# MCU.net
KiCad netlist of a schematic drawn in Altium Designer
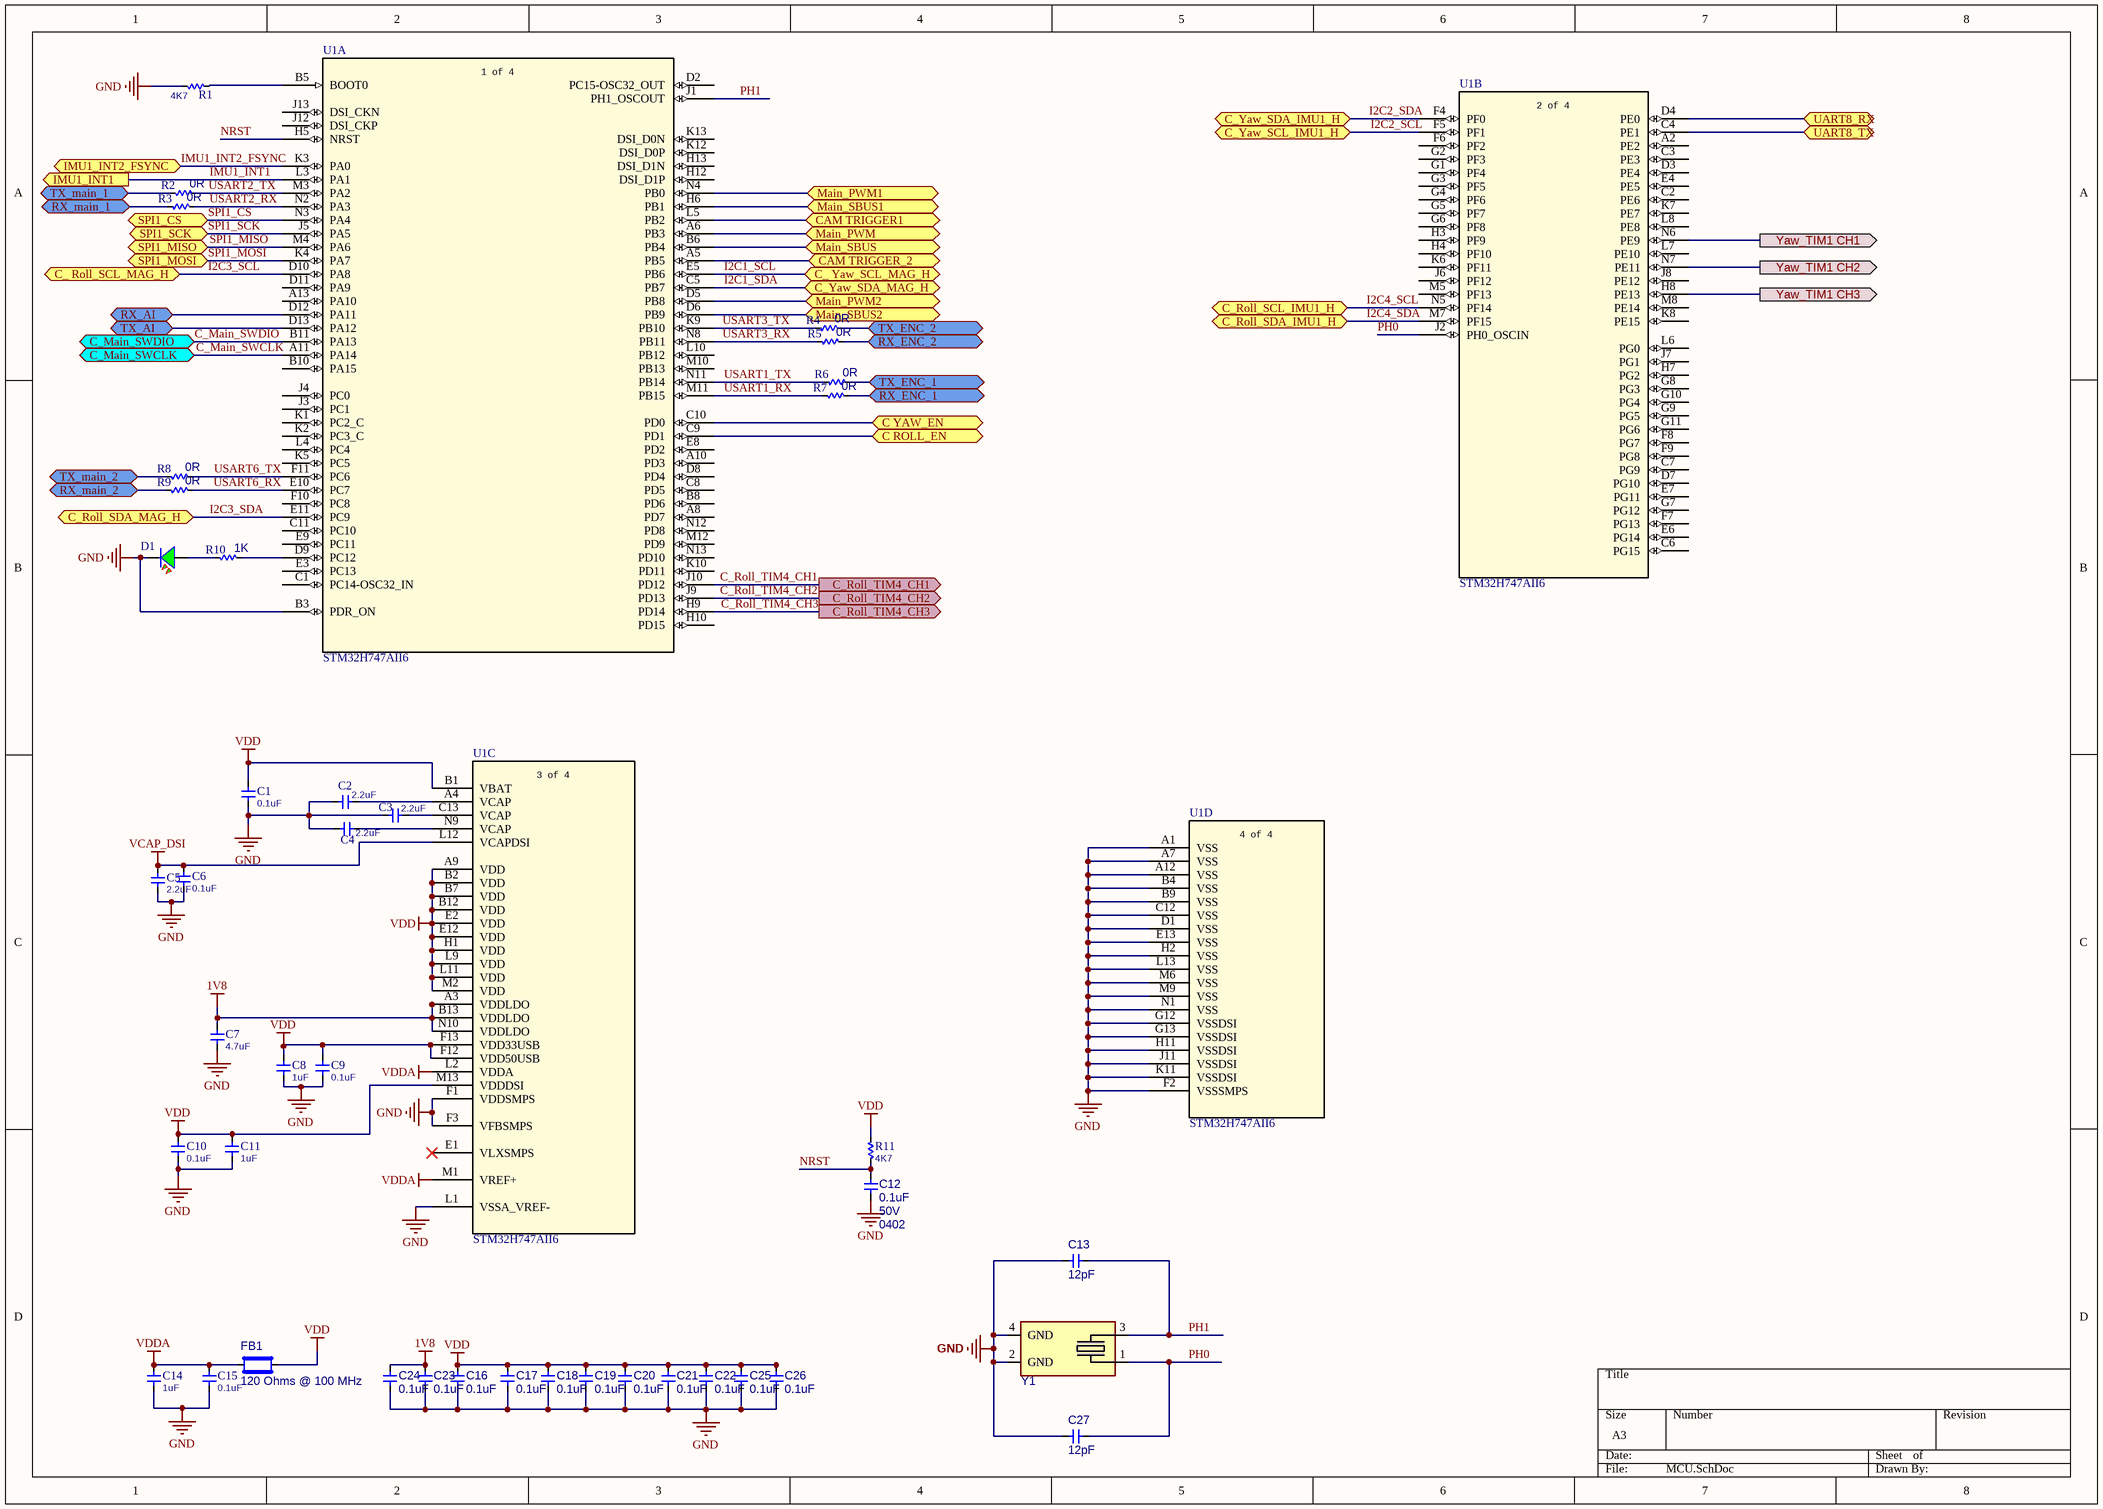
[diagram p0: MCU.SchDoc]

(export (version "E")
  (design (tool "Eeschema 10.0.6"))
  (components
    (comp (ref "C1")
      (value "0.1uF")
      (footprint "CAP0402")
      (description "Cap 0402")
      (fields (field (name "MP") "add later") (field (name "Comment") "CAP0402"))
      (libsource (lib "RTR") (part "CAP0402"))
    )
    (comp (ref "C2")
      (value "2.2uF")
      (footprint "CAP0402")
      (description "Cap 0402")
      (fields (field (name "MP") "add later") (field (name "Comment") "CAP0402"))
      (libsource (lib "RTR") (part "CAP0402"))
    )
    (comp (ref "C3")
      (value "2.2uF")
      (footprint "CAP0402")
      (description "Cap 0402")
      (fields (field (name "MP") "add later") (field (name "Comment") "CAP0402"))
      (libsource (lib "RTR") (part "CAP0402"))
    )
    (comp (ref "C4")
      (value "2.2uF")
      (footprint "CAP0402")
      (description "Cap 0402")
      (fields (field (name "MP") "add later") (field (name "Comment") "CAP0402"))
      (libsource (lib "RTR") (part "CAP0402"))
    )
    (comp (ref "C5")
      (value "2.2uF")
      (footprint "CAP0402")
      (description "Cap 0402")
      (fields (field (name "MP") "add later") (field (name "Comment") "CAP0402"))
      (libsource (lib "RTR") (part "CAP0402"))
    )
    (comp (ref "C6")
      (value "0.1uF")
      (footprint "CAP0402")
      (description "Cap 0402")
      (fields (field (name "MP") "add later") (field (name "Comment") "CAP0402"))
      (libsource (lib "RTR") (part "CAP0402"))
    )
    (comp (ref "C7")
      (value "4.7uF")
      (footprint "CAP0402")
      (description "Cap 0402")
      (fields (field (name "MP") "add later") (field (name "Comment") "CAP0402"))
      (libsource (lib "RTR") (part "CAP0402"))
    )
    (comp (ref "C8")
      (value "1uF")
      (footprint "CAP0402")
      (description "Cap 0402")
      (fields (field (name "MP") "add later") (field (name "Comment") "CAP0402"))
      (libsource (lib "RTR") (part "CAP0402"))
    )
    (comp (ref "C9")
      (value "0.1uF")
      (footprint "CAP0402")
      (description "Cap 0402")
      (fields (field (name "MP") "add later") (field (name "Comment") "CAP0402"))
      (libsource (lib "RTR") (part "CAP0402"))
    )
    (comp (ref "C10")
      (value "0.1uF")
      (footprint "CAP0402")
      (description "Cap 0402")
      (fields (field (name "MP") "add later") (field (name "Comment") "CAP0402"))
      (libsource (lib "RTR") (part "CAP0402"))
    )
    (comp (ref "C11")
      (value "1uF")
      (footprint "CAP0402")
      (description "Cap 0402")
      (fields (field (name "MP") "add later") (field (name "Comment") "CAP0402"))
      (libsource (lib "RTR") (part "CAP0402"))
    )
    (comp (ref "C12")
      (value "0.1uF")
      (footprint "CAP0402")
      (description "Cap 0.1uF 50V 0402")
      (fields
        (field (name "MP") "CC0402KRX5R9BB104")
        (field (name "VOLTAGE") "50V")
        (field (name "PACKAGE") "0402")
        (field (name "Comment") "CAP0402 0.1uF 50V")
      )
      (libsource (lib "RTR") (part "CAP0402 0.1uF 50V"))
    )
    (comp (ref "C13")
      (value "12pF")
      (footprint "CAP0402")
      (description "Cap 12pF 50V 0402")
      (fields (field (name "Comment") "CAP0402 12pF 50V"))
      (libsource (lib "RTR") (part "CAP0402 12pF 50V"))
    )
    (comp (ref "C14")
      (value "1uF")
      (footprint "CAP0402")
      (description "Cap 0402")
      (fields (field (name "MP") "add later") (field (name "Comment") "CAP0402"))
      (libsource (lib "RTR") (part "CAP0402"))
    )
    (comp (ref "C15")
      (value "0.1uF")
      (footprint "CAP0402")
      (description "Cap 0402")
      (fields (field (name "MP") "add later") (field (name "Comment") "CAP0402"))
      (libsource (lib "RTR") (part "CAP0402"))
    )
    (comp (ref "C16")
      (value "0.1uF")
      (footprint "CAP0402")
      (description "Cap 0.1uF 50V 0402")
      (fields (field (name "MP") "CC0402KRX5R9BB104") (field (name "VOLTAGE") "50V"))
      (libsource (lib "RTR") (part "CAP0402 0.1uF 50V"))
    )
    (comp (ref "C17")
      (value "0.1uF")
      (footprint "CAP0402")
      (description "Cap 0.1uF 50V 0402")
      (fields (field (name "MP") "CC0402KRX5R9BB104") (field (name "VOLTAGE") "50V"))
      (libsource (lib "RTR") (part "CAP0402 0.1uF 50V"))
    )
    (comp (ref "C18")
      (value "0.1uF")
      (footprint "CAP0402")
      (description "Cap 0.1uF 50V 0402")
      (fields (field (name "MP") "CC0402KRX5R9BB104") (field (name "VOLTAGE") "50V"))
      (libsource (lib "RTR") (part "CAP0402 0.1uF 50V"))
    )
    (comp (ref "C19")
      (value "0.1uF")
      (footprint "CAP0402")
      (description "Cap 0.1uF 50V 0402")
      (fields (field (name "MP") "CC0402KRX5R9BB104") (field (name "VOLTAGE") "50V"))
      (libsource (lib "RTR") (part "CAP0402 0.1uF 50V"))
    )
    (comp (ref "C20")
      (value "0.1uF")
      (footprint "CAP0402")
      (description "Cap 0.1uF 50V 0402")
      (fields (field (name "MP") "CC0402KRX5R9BB104") (field (name "VOLTAGE") "50V"))
      (libsource (lib "RTR") (part "CAP0402 0.1uF 50V"))
    )
    (comp (ref "C21")
      (value "0.1uF")
      (footprint "CAP0402")
      (description "Cap 0.1uF 50V 0402")
      (fields (field (name "MP") "CC0402KRX5R9BB104") (field (name "VOLTAGE") "50V"))
      (libsource (lib "RTR") (part "CAP0402 0.1uF 50V"))
    )
    (comp (ref "C22")
      (value "0.1uF")
      (footprint "CAP0402")
      (description "Cap 0.1uF 50V 0402")
      (fields (field (name "MP") "CC0402KRX5R9BB104") (field (name "VOLTAGE") "50V"))
      (libsource (lib "RTR") (part "CAP0402 0.1uF 50V"))
    )
    (comp (ref "C23")
      (value "0.1uF")
      (footprint "CAP0402")
      (description "Cap 0.1uF 50V 0402")
      (fields (field (name "MP") "CC0402KRX5R9BB104") (field (name "VOLTAGE") "50V"))
      (libsource (lib "RTR") (part "CAP0402 0.1uF 50V"))
    )
    (comp (ref "C24")
      (value "0.1uF")
      (footprint "CAP0402")
      (description "Cap 0.1uF 50V 0402")
      (fields (field (name "MP") "CC0402KRX5R9BB104") (field (name "VOLTAGE") "50V"))
      (libsource (lib "RTR") (part "CAP0402 0.1uF 50V"))
    )
    (comp (ref "C25")
      (value "0.1uF")
      (footprint "CAP0402")
      (description "Cap 0.1uF 50V 0402")
      (fields (field (name "MP") "CC0402KRX5R9BB104") (field (name "VOLTAGE") "50V"))
      (libsource (lib "RTR") (part "CAP0402 0.1uF 50V"))
    )
    (comp (ref "C26")
      (value "0.1uF")
      (footprint "CAP0402")
      (description "Cap 0.1uF 50V 0402")
      (fields (field (name "MP") "CC0402KRX5R9BB104") (field (name "VOLTAGE") "50V"))
      (libsource (lib "RTR") (part "CAP0402 0.1uF 50V"))
    )
    (comp (ref "C27")
      (value "12pF")
      (footprint "CAP0402")
      (description "Cap 12pF 50V 0402")
      (fields (field (name "Comment") "CAP0402 12pF 50V"))
      (libsource (lib "RTR") (part "CAP0402 12pF 50V"))
    )
    (comp (ref "D1")
      (value "SML-310MTT86")
      (footprint "LED0603 GREEN")
      (description "LED GREEN CLEAR 0603 SMD")
      (libsource (lib "HeraJetson_Modified") (part "CMP-01130-2"))
    )
    (comp (ref "FB1")
      (value "BLM15PX121SZ1D")
      (footprint "FERRIT0402")
      (description "120 Ohms @ 100 MHz 1 Power Line Ferrite Bead 0402 (1005 Metric) 2A 55mOhm")
      (fields (field (name "IMPEDANCE @ FREQUENCY") "120 Ohms @ 100 MHz"))
      (libsource (lib "RTR") (part "BLM15PX121SZ1D"))
    )
    (comp (ref "R1")
      (value "4K7")
      (footprint "RES0402")
      (description "RES 4K7 0402")
      (fields (field (name "MP") "RC0402JR-074K7L") (field (name "Comment") "RES0402 4K7"))
      (libsource (lib "RTR") (part "RES0402 4K7"))
    )
    (comp (ref "R2")
      (value "0R")
      (footprint "RES0402")
      (description "RES 0R 0402")
      (fields (field (name "MP") "RC0402JR-070RL") (field (name "Comment") "RES0402 0R"))
      (libsource (lib "RTR") (part "RES0402 0R"))
    )
    (comp (ref "R3")
      (value "0R")
      (footprint "RES0402")
      (description "RES 0R 0402")
      (fields (field (name "MP") "RC0402JR-070RL") (field (name "Comment") "RES0402 0R"))
      (libsource (lib "RTR") (part "RES0402 0R"))
    )
    (comp (ref "R4")
      (value "0R")
      (footprint "RES0402")
      (description "RES 0R 0402")
      (fields (field (name "MP") "RC0402JR-070RL") (field (name "Comment") "RES0402 0R"))
      (libsource (lib "RTR") (part "RES0402 0R"))
    )
    (comp (ref "R5")
      (value "0R")
      (footprint "RES0402")
      (description "RES 0R 0402")
      (fields (field (name "MP") "RC0402JR-070RL") (field (name "Comment") "RES0402 0R"))
      (libsource (lib "RTR") (part "RES0402 0R"))
    )
    (comp (ref "R6")
      (value "0R")
      (footprint "RES0402")
      (description "RES 0R 0402")
      (fields (field (name "MP") "RC0402JR-070RL") (field (name "Comment") "RES0402 0R"))
      (libsource (lib "RTR") (part "RES0402 0R"))
    )
    (comp (ref "R7")
      (value "0R")
      (footprint "RES0402")
      (description "RES 0R 0402")
      (fields (field (name "MP") "RC0402JR-070RL") (field (name "Comment") "RES0402 0R"))
      (libsource (lib "RTR") (part "RES0402 0R"))
    )
    (comp (ref "R8")
      (value "0R")
      (footprint "RES0402")
      (description "RES 0R 0402")
      (fields (field (name "MP") "RC0402JR-070RL") (field (name "Comment") "RES0402 0R"))
      (libsource (lib "RTR") (part "RES0402 0R"))
    )
    (comp (ref "R9")
      (value "0R")
      (footprint "RES0402")
      (description "RES 0R 0402")
      (fields (field (name "MP") "RC0402JR-070RL") (field (name "Comment") "RES0402 0R"))
      (libsource (lib "RTR") (part "RES0402 0R"))
    )
    (comp (ref "R10")
      (value "1K")
      (footprint "RES0402")
      (description "RES 0R 0402")
      (fields (field (name "MP") "RC0402JR-070RL") (field (name "Comment") "RES0402 0R"))
      (libsource (lib "RTR") (part "RES0402 0R"))
    )
    (comp (ref "R11")
      (value "4K7")
      (footprint "RES0402")
      (description "RES 4K7 0402")
      (fields (field (name "MP") "RC0402JR-074K7L") (field (name "Comment") "RES0402 4K7"))
      (libsource (lib "RTR") (part "RES0402 4K7"))
    )
    (comp (ref "U1")
      (value "STM32H747AII6")
      (footprint "UFBGA169")
      (fields (field (name "COPYRIGHT") "Copyright (C) 2026 Ultra Librarian. All rights reserved."))
      (libsource (lib "RTR") (part "STM32H747AII6"))
    )
    (comp (ref "Y1")
      (value "ECS-240-12-37B-CKY-TR")
      (footprint "XTAL_ECS-240-12-37B-CKY-TR")
      (description "Crystal 24 MHz ±10ppm 12pF 50 Ohms 4-SMD, No Lead")
      (libsource (lib "RTR") (part "ECS-240-12-37B-CKY-TR"))
    )
  )
  (nets
    (net (code "1") (name "/C ROLL_EN") (class "Default")
      (node (ref "U1") (pin "C9") (pinfunction "PD1_C9") (pintype "bidirectional"))
    )
    (net (code "2") (name "/C YAW_EN") (class "Default")
      (node (ref "U1") (pin "C10") (pinfunction "PD0_C10") (pintype "bidirectional"))
    )
    (net (code "3") (name "/CAM TRIGGER1") (class "Default")
      (node (ref "U1") (pin "L5") (pinfunction "PB2_L5") (pintype "bidirectional"))
    )
    (net (code "4") (name "/CAM TRIGGER_2") (class "Default")
      (node (ref "U1") (pin "A5") (pinfunction "PB5_A5") (pintype "bidirectional"))
    )
    (net (code "5") (name "/C_Main_SWCLK") (class "Default")
      (node (ref "U1") (pin "A11") (pinfunction "PA14_A11") (pintype "bidirectional"))
    )
    (net (code "6") (name "/C_Main_SWDIO") (class "Default")
      (node (ref "U1") (pin "B11") (pinfunction "PA13_B11") (pintype "bidirectional"))
    )
    (net (code "7") (name "/C_Roll_TIM4_CH1") (class "Default")
      (node (ref "U1") (pin "J10") (pinfunction "PD12_J10") (pintype "bidirectional"))
    )
    (net (code "8") (name "/C_Roll_TIM4_CH2") (class "Default")
      (node (ref "U1") (pin "J9") (pinfunction "PD13_J9") (pintype "bidirectional"))
    )
    (net (code "9") (name "/C_Roll_TIM4_CH3") (class "Default")
      (node (ref "U1") (pin "H9") (pinfunction "PD14_H9") (pintype "bidirectional"))
    )
    (net (code "10") (name "/I2C1_SCL") (class "Default")
      (node (ref "U1") (pin "E5") (pinfunction "PB6_E5") (pintype "bidirectional"))
    )
    (net (code "11") (name "/I2C1_SDA") (class "Default")
      (node (ref "U1") (pin "C5") (pinfunction "PB7_C5") (pintype "bidirectional"))
    )
    (net (code "12") (name "/I2C2_SCL") (class "Default")
      (node (ref "U1") (pin "F5") (pinfunction "PF1_F5") (pintype "bidirectional"))
    )
    (net (code "13") (name "/I2C2_SDA") (class "Default")
      (node (ref "U1") (pin "F4") (pinfunction "PF0_F4") (pintype "bidirectional"))
    )
    (net (code "14") (name "/I2C3_SCL") (class "Default")
      (node (ref "U1") (pin "D10") (pinfunction "PA8_D10") (pintype "bidirectional"))
    )
    (net (code "15") (name "/I2C3_SDA") (class "Default")
      (node (ref "U1") (pin "E11") (pinfunction "PC9_E11") (pintype "bidirectional"))
    )
    (net (code "16") (name "/I2C4_SCL") (class "Default")
      (node (ref "U1") (pin "N5") (pinfunction "PF14_N5") (pintype "bidirectional"))
    )
    (net (code "17") (name "/I2C4_SDA") (class "Default")
      (node (ref "U1") (pin "M7") (pinfunction "PF15_M7") (pintype "bidirectional"))
    )
    (net (code "18") (name "/IMU1_INT1") (class "Default")
      (node (ref "U1") (pin "L3") (pinfunction "PA1_L3") (pintype "bidirectional"))
    )
    (net (code "19") (name "/IMU1_INT2_FSYNC") (class "Default")
      (node (ref "U1") (pin "K3") (pinfunction "PA0_K3") (pintype "bidirectional"))
    )
    (net (code "20") (name "/Main_PWM") (class "Default")
      (node (ref "U1") (pin "A6") (pinfunction "PB3_A6") (pintype "bidirectional"))
    )
    (net (code "21") (name "/Main_PWM1") (class "Default")
      (node (ref "U1") (pin "N4") (pinfunction "PB0_N4") (pintype "bidirectional"))
    )
    (net (code "22") (name "/Main_PWM2") (class "Default")
      (node (ref "U1") (pin "D5") (pinfunction "PB8_D5") (pintype "bidirectional"))
    )
    (net (code "23") (name "/Main_SBUS") (class "Default")
      (node (ref "U1") (pin "B6") (pinfunction "PB4_B6") (pintype "bidirectional"))
    )
    (net (code "24") (name "/Main_SBUS1") (class "Default")
      (node (ref "U1") (pin "H6") (pinfunction "PB1_H6") (pintype "bidirectional"))
    )
    (net (code "25") (name "/Main_SBUS2") (class "Default")
      (node (ref "U1") (pin "D6") (pinfunction "PB9_D6") (pintype "bidirectional"))
    )
    (net (code "26") (name "/NRST") (class "Default")
      (node (ref "C12") (pin "2") (pinfunction "2_2") (pintype "passive"))
      (node (ref "R11") (pin "1") (pinfunction "1_1") (pintype "passive"))
      (node (ref "U1") (pin "H5") (pinfunction "NRST_H5") (pintype "bidirectional"))
    )
    (net (code "27") (name "/PH0") (class "Default")
      (node (ref "C27") (pin "1") (pinfunction "1_1") (pintype "passive"))
      (node (ref "U1") (pin "J2") (pinfunction "PH0_OSCIN_J2") (pintype "bidirectional"))
      (node (ref "Y1") (pin "1") (pinfunction "IO_1") (pintype "passive"))
    )
    (net (code "28") (name "/PH1") (class "Default")
      (node (ref "C13") (pin "1") (pinfunction "1_1") (pintype "passive"))
      (node (ref "U1") (pin "J1") (pinfunction "PH1_OSCOUT_J1") (pintype "bidirectional"))
      (node (ref "Y1") (pin "3") (pinfunction "IO_3") (pintype "passive"))
    )
    (net (code "29") (name "/RX_AI") (class "Default")
      (node (ref "U1") (pin "D12") (pinfunction "PA11_D12") (pintype "bidirectional"))
    )
    (net (code "30") (name "/RX_ENC_1") (class "Default")
      (node (ref "R7") (pin "2") (pinfunction "2_2") (pintype "passive"))
    )
    (net (code "31") (name "/RX_ENC_2") (class "Default")
      (node (ref "R5") (pin "2") (pinfunction "2_2") (pintype "passive"))
    )
    (net (code "32") (name "/RX_main_1") (class "Default")
      (node (ref "R3") (pin "1") (pinfunction "1_1") (pintype "passive"))
    )
    (net (code "33") (name "/RX_main_2") (class "Default")
      (node (ref "R9") (pin "1") (pinfunction "1_1") (pintype "passive"))
    )
    (net (code "34") (name "/SPI1_CS") (class "Default")
      (node (ref "U1") (pin "N3") (pinfunction "PA4_N3") (pintype "bidirectional"))
    )
    (net (code "35") (name "/SPI1_MISO") (class "Default")
      (node (ref "U1") (pin "M4") (pinfunction "PA6_M4") (pintype "bidirectional"))
    )
    (net (code "36") (name "/SPI1_MOSI") (class "Default")
      (node (ref "U1") (pin "K4") (pinfunction "PA7_K4") (pintype "bidirectional"))
    )
    (net (code "37") (name "/SPI1_SCK") (class "Default")
      (node (ref "U1") (pin "J5") (pinfunction "PA5_J5") (pintype "bidirectional"))
    )
    (net (code "38") (name "/TX_AI") (class "Default")
      (node (ref "U1") (pin "D13") (pinfunction "PA12_D13") (pintype "bidirectional"))
    )
    (net (code "39") (name "/TX_ENC_1") (class "Default")
      (node (ref "R6") (pin "2") (pinfunction "2_2") (pintype "passive"))
    )
    (net (code "40") (name "/TX_ENC_2") (class "Default")
      (node (ref "R4") (pin "2") (pinfunction "2_2") (pintype "passive"))
    )
    (net (code "41") (name "/TX_main_1") (class "Default")
      (node (ref "R2") (pin "1") (pinfunction "1_1") (pintype "passive"))
    )
    (net (code "42") (name "/TX_main_2") (class "Default")
      (node (ref "R8") (pin "1") (pinfunction "1_1") (pintype "passive"))
    )
    (net (code "43") (name "/UART8_RX") (class "Default")
      (node (ref "U1") (pin "D4") (pinfunction "PE0_D4") (pintype "bidirectional"))
    )
    (net (code "44") (name "/UART8_TX") (class "Default")
      (node (ref "U1") (pin "C4") (pinfunction "PE1_C4") (pintype "bidirectional"))
    )
    (net (code "45") (name "/USART1_RX") (class "Default")
      (node (ref "R7") (pin "1") (pinfunction "1_1") (pintype "passive"))
      (node (ref "U1") (pin "M11") (pinfunction "PB15_M11") (pintype "bidirectional"))
    )
    (net (code "46") (name "/USART1_TX") (class "Default")
      (node (ref "R6") (pin "1") (pinfunction "1_1") (pintype "passive"))
      (node (ref "U1") (pin "N11") (pinfunction "PB14_N11") (pintype "bidirectional"))
    )
    (net (code "47") (name "/USART2_RX") (class "Default")
      (node (ref "R3") (pin "2") (pinfunction "2_2") (pintype "passive"))
      (node (ref "U1") (pin "N2") (pinfunction "PA3_N2") (pintype "bidirectional"))
    )
    (net (code "48") (name "/USART2_TX") (class "Default")
      (node (ref "R2") (pin "2") (pinfunction "2_2") (pintype "passive"))
      (node (ref "U1") (pin "M3") (pinfunction "PA2_M3") (pintype "bidirectional"))
    )
    (net (code "49") (name "/USART3_RX") (class "Default")
      (node (ref "R5") (pin "1") (pinfunction "1_1") (pintype "passive"))
      (node (ref "U1") (pin "N8") (pinfunction "PB11_N8") (pintype "bidirectional"))
    )
    (net (code "50") (name "/USART3_TX") (class "Default")
      (node (ref "R4") (pin "1") (pinfunction "1_1") (pintype "passive"))
      (node (ref "U1") (pin "K9") (pinfunction "PB10_K9") (pintype "bidirectional"))
    )
    (net (code "51") (name "/USART6_RX") (class "Default")
      (node (ref "R9") (pin "2") (pinfunction "2_2") (pintype "passive"))
      (node (ref "U1") (pin "E10") (pinfunction "PC7_E10") (pintype "bidirectional"))
    )
    (net (code "52") (name "/USART6_TX") (class "Default")
      (node (ref "R8") (pin "2") (pinfunction "2_2") (pintype "passive"))
      (node (ref "U1") (pin "F11") (pinfunction "PC6_F11") (pintype "bidirectional"))
    )
    (net (code "53") (name "/Yaw_TIM1 CH1") (class "Default")
      (node (ref "U1") (pin "N6") (pinfunction "PE9_N6") (pintype "bidirectional"))
    )
    (net (code "54") (name "/Yaw_TIM1 CH2") (class "Default")
      (node (ref "U1") (pin "N7") (pinfunction "PE11_N7") (pintype "bidirectional"))
    )
    (net (code "55") (name "/Yaw_TIM1 CH3") (class "Default")
      (node (ref "U1") (pin "H8") (pinfunction "PE13_H8") (pintype "bidirectional"))
    )
    (net (code "56") (name "1V8") (class "Default")
      (node (ref "C23") (pin "2") (pinfunction "2_2") (pintype "passive"))
      (node (ref "C24") (pin "2") (pinfunction "2_2") (pintype "passive"))
      (node (ref "C7") (pin "2") (pinfunction "2_2") (pintype "passive"))
      (node (ref "U1") (pin "A3") (pinfunction "VDDLDO_A3") (pintype "power_in"))
      (node (ref "U1") (pin "B13") (pinfunction "VDDLDO_B13") (pintype "power_in"))
      (node (ref "U1") (pin "N10") (pinfunction "VDDLDO_N10") (pintype "power_in"))
    )
    (net (code "57") (name "GND") (class "Default")
      (node (ref "C1") (pin "1") (pinfunction "1_1") (pintype "passive"))
      (node (ref "C10") (pin "1") (pinfunction "1_1") (pintype "passive"))
      (node (ref "C11") (pin "1") (pinfunction "1_1") (pintype "passive"))
      (node (ref "C12") (pin "1") (pinfunction "1_1") (pintype "passive"))
      (node (ref "C13") (pin "2") (pinfunction "2_2") (pintype "passive"))
      (node (ref "C14") (pin "1") (pinfunction "1_1") (pintype "passive"))
      (node (ref "C15") (pin "1") (pinfunction "1_1") (pintype "passive"))
      (node (ref "C16") (pin "1") (pinfunction "1_1") (pintype "passive"))
      (node (ref "C17") (pin "1") (pinfunction "1_1") (pintype "passive"))
      (node (ref "C18") (pin "1") (pinfunction "1_1") (pintype "passive"))
      (node (ref "C19") (pin "1") (pinfunction "1_1") (pintype "passive"))
      (node (ref "C2") (pin "1") (pinfunction "1_1") (pintype "passive"))
      (node (ref "C20") (pin "1") (pinfunction "1_1") (pintype "passive"))
      (node (ref "C21") (pin "1") (pinfunction "1_1") (pintype "passive"))
      (node (ref "C22") (pin "1") (pinfunction "1_1") (pintype "passive"))
      (node (ref "C23") (pin "1") (pinfunction "1_1") (pintype "passive"))
      (node (ref "C24") (pin "1") (pinfunction "1_1") (pintype "passive"))
      (node (ref "C25") (pin "1") (pinfunction "1_1") (pintype "passive"))
      (node (ref "C26") (pin "1") (pinfunction "1_1") (pintype "passive"))
      (node (ref "C27") (pin "2") (pinfunction "2_2") (pintype "passive"))
      (node (ref "C3") (pin "1") (pinfunction "1_1") (pintype "passive"))
      (node (ref "C4") (pin "1") (pinfunction "1_1") (pintype "passive"))
      (node (ref "C5") (pin "1") (pinfunction "1_1") (pintype "passive"))
      (node (ref "C6") (pin "1") (pinfunction "1_1") (pintype "passive"))
      (node (ref "C7") (pin "1") (pinfunction "1_1") (pintype "passive"))
      (node (ref "C8") (pin "1") (pinfunction "1_1") (pintype "passive"))
      (node (ref "C9") (pin "1") (pinfunction "1_1") (pintype "passive"))
      (node (ref "D1") (pin "1") (pinfunction "1_1") (pintype "passive"))
      (node (ref "R1") (pin "1") (pinfunction "1_1") (pintype "passive"))
      (node (ref "U1") (pin "A1") (pinfunction "VSS_A1") (pintype "power_in"))
      (node (ref "U1") (pin "A12") (pinfunction "VSS_A12") (pintype "power_in"))
      (node (ref "U1") (pin "A7") (pinfunction "VSS_A7") (pintype "power_in"))
      (node (ref "U1") (pin "B3") (pinfunction "PDR_ON_B3") (pintype "bidirectional"))
      (node (ref "U1") (pin "B4") (pinfunction "VSS_B4") (pintype "power_in"))
      (node (ref "U1") (pin "B9") (pinfunction "VSS_B9") (pintype "power_in"))
      (node (ref "U1") (pin "C12") (pinfunction "VSS_C12") (pintype "power_in"))
      (node (ref "U1") (pin "D1") (pinfunction "VSS_D1") (pintype "power_in"))
      (node (ref "U1") (pin "E13") (pinfunction "VSS_E13") (pintype "power_in"))
      (node (ref "U1") (pin "F1") (pinfunction "VDDSMPS_F1") (pintype "power_in"))
      (node (ref "U1") (pin "F2") (pinfunction "VSSSMPS_F2") (pintype "power_in"))
      (node (ref "U1") (pin "F3") (pinfunction "VFBSMPS_F3") (pintype "power_in"))
      (node (ref "U1") (pin "G12") (pinfunction "VSSDSI_G12") (pintype "power_in"))
      (node (ref "U1") (pin "G13") (pinfunction "VSSDSI_G13") (pintype "power_in"))
      (node (ref "U1") (pin "H11") (pinfunction "VSSDSI_H11") (pintype "power_in"))
      (node (ref "U1") (pin "H2") (pinfunction "VSS_H2") (pintype "power_in"))
      (node (ref "U1") (pin "J11") (pinfunction "VSSDSI_J11") (pintype "power_in"))
      (node (ref "U1") (pin "K11") (pinfunction "VSSDSI_K11") (pintype "power_in"))
      (node (ref "U1") (pin "L1") (pinfunction "VSSA_VREF-_L1") (pintype "power_in"))
      (node (ref "U1") (pin "L13") (pinfunction "VSS_L13") (pintype "power_in"))
      (node (ref "U1") (pin "M6") (pinfunction "VSS_M6") (pintype "power_in"))
      (node (ref "U1") (pin "M9") (pinfunction "VSS_M9") (pintype "power_in"))
      (node (ref "U1") (pin "N1") (pinfunction "VSS_N1") (pintype "power_in"))
      (node (ref "Y1") (pin "2") (pinfunction "GND_2") (pintype "passive"))
      (node (ref "Y1") (pin "4") (pinfunction "GND_4") (pintype "passive"))
    )
    (net (code "58") (name "Net-(C2-Pad2)") (class "Default")
      (node (ref "C2") (pin "2") (pinfunction "2_2") (pintype "passive"))
      (node (ref "U1") (pin "A4") (pinfunction "VCAP_A4") (pintype "power_in"))
    )
    (net (code "59") (name "Net-(C3-Pad2)") (class "Default")
      (node (ref "C3") (pin "2") (pinfunction "2_2") (pintype "passive"))
      (node (ref "U1") (pin "C13") (pinfunction "VCAP_C13") (pintype "power_in"))
    )
    (net (code "60") (name "Net-(C4-Pad2)") (class "Default")
      (node (ref "C4") (pin "2") (pinfunction "2_2") (pintype "passive"))
      (node (ref "U1") (pin "N9") (pinfunction "VCAP_N9") (pintype "power_in"))
    )
    (net (code "61") (name "Net-(D1-Pad2)") (class "Default")
      (node (ref "D1") (pin "2") (pinfunction "2_2") (pintype "passive"))
      (node (ref "R10") (pin "1") (pinfunction "1_1") (pintype "passive"))
    )
    (net (code "62") (name "Net-(U1A-BOOT0)") (class "Default")
      (node (ref "R1") (pin "2") (pinfunction "2_2") (pintype "passive"))
      (node (ref "U1") (pin "B5") (pinfunction "BOOT0_B5") (pintype "input"))
    )
    (net (code "63") (name "Net-(U1A-PC12)") (class "Default")
      (node (ref "R10") (pin "2") (pinfunction "2_2") (pintype "passive"))
      (node (ref "U1") (pin "D9") (pinfunction "PC12_D9") (pintype "bidirectional"))
    )
    (net (code "64") (name "VCAP_DSI") (class "Default")
      (node (ref "C5") (pin "2") (pinfunction "2_2") (pintype "passive"))
      (node (ref "C6") (pin "2") (pinfunction "2_2") (pintype "passive"))
      (node (ref "U1") (pin "L12") (pinfunction "VCAPDSI_L12") (pintype "power_in"))
    )
    (net (code "65") (name "VDD") (class "Default")
      (node (ref "C1") (pin "2") (pinfunction "2_2") (pintype "passive"))
      (node (ref "C10") (pin "2") (pinfunction "2_2") (pintype "passive"))
      (node (ref "C11") (pin "2") (pinfunction "2_2") (pintype "passive"))
      (node (ref "C16") (pin "2") (pinfunction "2_2") (pintype "passive"))
      (node (ref "C17") (pin "2") (pinfunction "2_2") (pintype "passive"))
      (node (ref "C18") (pin "2") (pinfunction "2_2") (pintype "passive"))
      (node (ref "C19") (pin "2") (pinfunction "2_2") (pintype "passive"))
      (node (ref "C20") (pin "2") (pinfunction "2_2") (pintype "passive"))
      (node (ref "C21") (pin "2") (pinfunction "2_2") (pintype "passive"))
      (node (ref "C22") (pin "2") (pinfunction "2_2") (pintype "passive"))
      (node (ref "C25") (pin "2") (pinfunction "2_2") (pintype "passive"))
      (node (ref "C26") (pin "2") (pinfunction "2_2") (pintype "passive"))
      (node (ref "C8") (pin "2") (pinfunction "2_2") (pintype "passive"))
      (node (ref "C9") (pin "2") (pinfunction "2_2") (pintype "passive"))
      (node (ref "FB1") (pin "2") (pinfunction "2_2") (pintype "passive"))
      (node (ref "R11") (pin "2") (pinfunction "2_2") (pintype "passive"))
      (node (ref "U1") (pin "A9") (pinfunction "VDD_A9") (pintype "power_in"))
      (node (ref "U1") (pin "B1") (pinfunction "VBAT_B1") (pintype "power_in"))
      (node (ref "U1") (pin "B12") (pinfunction "VDD_B12") (pintype "power_in"))
      (node (ref "U1") (pin "B2") (pinfunction "VDD_B2") (pintype "power_in"))
      (node (ref "U1") (pin "B7") (pinfunction "VDD_B7") (pintype "power_in"))
      (node (ref "U1") (pin "E12") (pinfunction "VDD_E12") (pintype "power_in"))
      (node (ref "U1") (pin "E2") (pinfunction "VDD_E2") (pintype "power_in"))
      (node (ref "U1") (pin "F12") (pinfunction "VDD50USB_F12") (pintype "power_in"))
      (node (ref "U1") (pin "F13") (pinfunction "VDD33USB_F13") (pintype "power_in"))
      (node (ref "U1") (pin "H1") (pinfunction "VDD_H1") (pintype "power_in"))
      (node (ref "U1") (pin "L11") (pinfunction "VDD_L11") (pintype "power_in"))
      (node (ref "U1") (pin "L9") (pinfunction "VDD_L9") (pintype "power_in"))
      (node (ref "U1") (pin "M13") (pinfunction "VDDDSI_M13") (pintype "power_in"))
      (node (ref "U1") (pin "M2") (pinfunction "VDD_M2") (pintype "power_in"))
    )
    (net (code "66") (name "VDDA") (class "Default")
      (node (ref "C14") (pin "2") (pinfunction "2_2") (pintype "passive"))
      (node (ref "C15") (pin "2") (pinfunction "2_2") (pintype "passive"))
      (node (ref "FB1") (pin "1") (pinfunction "1_1") (pintype "passive"))
      (node (ref "U1") (pin "L2") (pinfunction "VDDA_L2") (pintype "power_in"))
      (node (ref "U1") (pin "M1") (pinfunction "VREF+_M1") (pintype "power_in"))
    )
    (net (code "67") (name "unconnected-(U1A-DSI_CKN-PadJ13)") (class "Default")
      (node (ref "U1") (pin "J13") (pinfunction "DSI_CKN_J13") (pintype "bidirectional"))
    )
    (net (code "68") (name "unconnected-(U1A-DSI_CKP-PadJ12)") (class "Default")
      (node (ref "U1") (pin "J12") (pinfunction "DSI_CKP_J12") (pintype "bidirectional"))
    )
    (net (code "69") (name "unconnected-(U1A-DSI_D0N-PadK13)") (class "Default")
      (node (ref "U1") (pin "K13") (pinfunction "DSI_D0N_K13") (pintype "bidirectional"))
    )
    (net (code "70") (name "unconnected-(U1A-DSI_D0P-PadK12)") (class "Default")
      (node (ref "U1") (pin "K12") (pinfunction "DSI_D0P_K12") (pintype "bidirectional"))
    )
    (net (code "71") (name "unconnected-(U1A-DSI_D1N-PadH13)") (class "Default")
      (node (ref "U1") (pin "H13") (pinfunction "DSI_D1N_H13") (pintype "bidirectional"))
    )
    (net (code "72") (name "unconnected-(U1A-DSI_D1P-PadH12)") (class "Default")
      (node (ref "U1") (pin "H12") (pinfunction "DSI_D1P_H12") (pintype "bidirectional"))
    )
    (net (code "73") (name "unconnected-(U1A-PA9-PadD11)") (class "Default")
      (node (ref "U1") (pin "D11") (pinfunction "PA9_D11") (pintype "bidirectional"))
    )
    (net (code "74") (name "unconnected-(U1A-PA10-PadA13)") (class "Default")
      (node (ref "U1") (pin "A13") (pinfunction "PA10_A13") (pintype "bidirectional"))
    )
    (net (code "75") (name "unconnected-(U1A-PA15-PadB10)") (class "Default")
      (node (ref "U1") (pin "B10") (pinfunction "PA15_B10") (pintype "bidirectional"))
    )
    (net (code "76") (name "unconnected-(U1A-PB12-PadL10)") (class "Default")
      (node (ref "U1") (pin "L10") (pinfunction "PB12_L10") (pintype "bidirectional"))
    )
    (net (code "77") (name "unconnected-(U1A-PB13-PadM10)") (class "Default")
      (node (ref "U1") (pin "M10") (pinfunction "PB13_M10") (pintype "bidirectional"))
    )
    (net (code "78") (name "unconnected-(U1A-PC0-PadJ4)") (class "Default")
      (node (ref "U1") (pin "J4") (pinfunction "PC0_J4") (pintype "bidirectional"))
    )
    (net (code "79") (name "unconnected-(U1A-PC1-PadJ3)") (class "Default")
      (node (ref "U1") (pin "J3") (pinfunction "PC1_J3") (pintype "bidirectional"))
    )
    (net (code "80") (name "unconnected-(U1A-PC2_C-PadK1)") (class "Default")
      (node (ref "U1") (pin "K1") (pinfunction "PC2_C_K1") (pintype "bidirectional"))
    )
    (net (code "81") (name "unconnected-(U1A-PC3_C-PadK2)") (class "Default")
      (node (ref "U1") (pin "K2") (pinfunction "PC3_C_K2") (pintype "bidirectional"))
    )
    (net (code "82") (name "unconnected-(U1A-PC4-PadL4)") (class "Default")
      (node (ref "U1") (pin "L4") (pinfunction "PC4_L4") (pintype "bidirectional"))
    )
    (net (code "83") (name "unconnected-(U1A-PC5-PadK5)") (class "Default")
      (node (ref "U1") (pin "K5") (pinfunction "PC5_K5") (pintype "bidirectional"))
    )
    (net (code "84") (name "unconnected-(U1A-PC8-PadF10)") (class "Default")
      (node (ref "U1") (pin "F10") (pinfunction "PC8_F10") (pintype "bidirectional"))
    )
    (net (code "85") (name "unconnected-(U1A-PC10-PadC11)") (class "Default")
      (node (ref "U1") (pin "C11") (pinfunction "PC10_C11") (pintype "bidirectional"))
    )
    (net (code "86") (name "unconnected-(U1A-PC11-PadE9)") (class "Default")
      (node (ref "U1") (pin "E9") (pinfunction "PC11_E9") (pintype "bidirectional"))
    )
    (net (code "87") (name "unconnected-(U1A-PC13-PadE3)") (class "Default")
      (node (ref "U1") (pin "E3") (pinfunction "PC13_E3") (pintype "bidirectional"))
    )
    (net (code "88") (name "unconnected-(U1A-PC14-OSC32_IN-PadC1)") (class "Default")
      (node (ref "U1") (pin "C1") (pinfunction "PC14-OSC32_IN_C1") (pintype "bidirectional"))
    )
    (net (code "89") (name "unconnected-(U1A-PC15-OSC32_OUT-PadD2)") (class "Default")
      (node (ref "U1") (pin "D2") (pinfunction "PC15-OSC32_OUT_D2") (pintype "bidirectional"))
    )
    (net (code "90") (name "unconnected-(U1A-PD2-PadE8)") (class "Default")
      (node (ref "U1") (pin "E8") (pinfunction "PD2_E8") (pintype "bidirectional"))
    )
    (net (code "91") (name "unconnected-(U1A-PD3-PadA10)") (class "Default")
      (node (ref "U1") (pin "A10") (pinfunction "PD3_A10") (pintype "bidirectional"))
    )
    (net (code "92") (name "unconnected-(U1A-PD4-PadD8)") (class "Default")
      (node (ref "U1") (pin "D8") (pinfunction "PD4_D8") (pintype "bidirectional"))
    )
    (net (code "93") (name "unconnected-(U1A-PD5-PadC8)") (class "Default")
      (node (ref "U1") (pin "C8") (pinfunction "PD5_C8") (pintype "bidirectional"))
    )
    (net (code "94") (name "unconnected-(U1A-PD6-PadB8)") (class "Default")
      (node (ref "U1") (pin "B8") (pinfunction "PD6_B8") (pintype "bidirectional"))
    )
    (net (code "95") (name "unconnected-(U1A-PD7-PadA8)") (class "Default")
      (node (ref "U1") (pin "A8") (pinfunction "PD7_A8") (pintype "bidirectional"))
    )
    (net (code "96") (name "unconnected-(U1A-PD8-PadN12)") (class "Default")
      (node (ref "U1") (pin "N12") (pinfunction "PD8_N12") (pintype "bidirectional"))
    )
    (net (code "97") (name "unconnected-(U1A-PD9-PadM12)") (class "Default")
      (node (ref "U1") (pin "M12") (pinfunction "PD9_M12") (pintype "bidirectional"))
    )
    (net (code "98") (name "unconnected-(U1A-PD10-PadN13)") (class "Default")
      (node (ref "U1") (pin "N13") (pinfunction "PD10_N13") (pintype "bidirectional"))
    )
    (net (code "99") (name "unconnected-(U1A-PD11-PadK10)") (class "Default")
      (node (ref "U1") (pin "K10") (pinfunction "PD11_K10") (pintype "bidirectional"))
    )
    (net (code "100") (name "unconnected-(U1A-PD15-PadH10)") (class "Default")
      (node (ref "U1") (pin "H10") (pinfunction "PD15_H10") (pintype "bidirectional"))
    )
    (net (code "101") (name "unconnected-(U1B-PE2-PadA2)") (class "Default")
      (node (ref "U1") (pin "A2") (pinfunction "PE2_A2") (pintype "bidirectional"))
    )
    (net (code "102") (name "unconnected-(U1B-PE3-PadC3)") (class "Default")
      (node (ref "U1") (pin "C3") (pinfunction "PE3_C3") (pintype "bidirectional"))
    )
    (net (code "103") (name "unconnected-(U1B-PE4-PadD3)") (class "Default")
      (node (ref "U1") (pin "D3") (pinfunction "PE4_D3") (pintype "bidirectional"))
    )
    (net (code "104") (name "unconnected-(U1B-PE5-PadE4)") (class "Default")
      (node (ref "U1") (pin "E4") (pinfunction "PE5_E4") (pintype "bidirectional"))
    )
    (net (code "105") (name "unconnected-(U1B-PE6-PadC2)") (class "Default")
      (node (ref "U1") (pin "C2") (pinfunction "PE6_C2") (pintype "bidirectional"))
    )
    (net (code "106") (name "unconnected-(U1B-PE7-PadK7)") (class "Default")
      (node (ref "U1") (pin "K7") (pinfunction "PE7_K7") (pintype "bidirectional"))
    )
    (net (code "107") (name "unconnected-(U1B-PE8-PadL8)") (class "Default")
      (node (ref "U1") (pin "L8") (pinfunction "PE8_L8") (pintype "bidirectional"))
    )
    (net (code "108") (name "unconnected-(U1B-PE10-PadL7)") (class "Default")
      (node (ref "U1") (pin "L7") (pinfunction "PE10_L7") (pintype "bidirectional"))
    )
    (net (code "109") (name "unconnected-(U1B-PE12-PadJ8)") (class "Default")
      (node (ref "U1") (pin "J8") (pinfunction "PE12_J8") (pintype "bidirectional"))
    )
    (net (code "110") (name "unconnected-(U1B-PE14-PadM8)") (class "Default")
      (node (ref "U1") (pin "M8") (pinfunction "PE14_M8") (pintype "bidirectional"))
    )
    (net (code "111") (name "unconnected-(U1B-PE15-PadK8)") (class "Default")
      (node (ref "U1") (pin "K8") (pinfunction "PE15_K8") (pintype "bidirectional"))
    )
    (net (code "112") (name "unconnected-(U1B-PF2-PadF6)") (class "Default")
      (node (ref "U1") (pin "F6") (pinfunction "PF2_F6") (pintype "bidirectional"))
    )
    (net (code "113") (name "unconnected-(U1B-PF3-PadG2)") (class "Default")
      (node (ref "U1") (pin "G2") (pinfunction "PF3_G2") (pintype "bidirectional"))
    )
    (net (code "114") (name "unconnected-(U1B-PF4-PadG1)") (class "Default")
      (node (ref "U1") (pin "G1") (pinfunction "PF4_G1") (pintype "bidirectional"))
    )
    (net (code "115") (name "unconnected-(U1B-PF5-PadG3)") (class "Default")
      (node (ref "U1") (pin "G3") (pinfunction "PF5_G3") (pintype "bidirectional"))
    )
    (net (code "116") (name "unconnected-(U1B-PF6-PadG4)") (class "Default")
      (node (ref "U1") (pin "G4") (pinfunction "PF6_G4") (pintype "bidirectional"))
    )
    (net (code "117") (name "unconnected-(U1B-PF7-PadG5)") (class "Default")
      (node (ref "U1") (pin "G5") (pinfunction "PF7_G5") (pintype "bidirectional"))
    )
    (net (code "118") (name "unconnected-(U1B-PF8-PadG6)") (class "Default")
      (node (ref "U1") (pin "G6") (pinfunction "PF8_G6") (pintype "bidirectional"))
    )
    (net (code "119") (name "unconnected-(U1B-PF9-PadH3)") (class "Default")
      (node (ref "U1") (pin "H3") (pinfunction "PF9_H3") (pintype "bidirectional"))
    )
    (net (code "120") (name "unconnected-(U1B-PF10-PadH4)") (class "Default")
      (node (ref "U1") (pin "H4") (pinfunction "PF10_H4") (pintype "bidirectional"))
    )
    (net (code "121") (name "unconnected-(U1B-PF11-PadK6)") (class "Default")
      (node (ref "U1") (pin "K6") (pinfunction "PF11_K6") (pintype "bidirectional"))
    )
    (net (code "122") (name "unconnected-(U1B-PF12-PadJ6)") (class "Default")
      (node (ref "U1") (pin "J6") (pinfunction "PF12_J6") (pintype "bidirectional"))
    )
    (net (code "123") (name "unconnected-(U1B-PF13-PadM5)") (class "Default")
      (node (ref "U1") (pin "M5") (pinfunction "PF13_M5") (pintype "bidirectional"))
    )
    (net (code "124") (name "unconnected-(U1B-PG0-PadL6)") (class "Default")
      (node (ref "U1") (pin "L6") (pinfunction "PG0_L6") (pintype "bidirectional"))
    )
    (net (code "125") (name "unconnected-(U1B-PG1-PadJ7)") (class "Default")
      (node (ref "U1") (pin "J7") (pinfunction "PG1_J7") (pintype "bidirectional"))
    )
    (net (code "126") (name "unconnected-(U1B-PG2-PadH7)") (class "Default")
      (node (ref "U1") (pin "H7") (pinfunction "PG2_H7") (pintype "bidirectional"))
    )
    (net (code "127") (name "unconnected-(U1B-PG3-PadG8)") (class "Default")
      (node (ref "U1") (pin "G8") (pinfunction "PG3_G8") (pintype "bidirectional"))
    )
    (net (code "128") (name "unconnected-(U1B-PG4-PadG10)") (class "Default")
      (node (ref "U1") (pin "G10") (pinfunction "PG4_G10") (pintype "bidirectional"))
    )
    (net (code "129") (name "unconnected-(U1B-PG5-PadG9)") (class "Default")
      (node (ref "U1") (pin "G9") (pinfunction "PG5_G9") (pintype "bidirectional"))
    )
    (net (code "130") (name "unconnected-(U1B-PG6-PadG11)") (class "Default")
      (node (ref "U1") (pin "G11") (pinfunction "PG6_G11") (pintype "bidirectional"))
    )
    (net (code "131") (name "unconnected-(U1B-PG7-PadF8)") (class "Default")
      (node (ref "U1") (pin "F8") (pinfunction "PG7_F8") (pintype "bidirectional"))
    )
    (net (code "132") (name "unconnected-(U1B-PG8-PadF9)") (class "Default")
      (node (ref "U1") (pin "F9") (pinfunction "PG8_F9") (pintype "bidirectional"))
    )
    (net (code "133") (name "unconnected-(U1B-PG9-PadC7)") (class "Default")
      (node (ref "U1") (pin "C7") (pinfunction "PG9_C7") (pintype "bidirectional"))
    )
    (net (code "134") (name "unconnected-(U1B-PG10-PadD7)") (class "Default")
      (node (ref "U1") (pin "D7") (pinfunction "PG10_D7") (pintype "bidirectional"))
    )
    (net (code "135") (name "unconnected-(U1B-PG11-PadE7)") (class "Default")
      (node (ref "U1") (pin "E7") (pinfunction "PG11_E7") (pintype "bidirectional"))
    )
    (net (code "136") (name "unconnected-(U1B-PG12-PadG7)") (class "Default")
      (node (ref "U1") (pin "G7") (pinfunction "PG12_G7") (pintype "bidirectional"))
    )
    (net (code "137") (name "unconnected-(U1B-PG13-PadF7)") (class "Default")
      (node (ref "U1") (pin "F7") (pinfunction "PG13_F7") (pintype "bidirectional"))
    )
    (net (code "138") (name "unconnected-(U1B-PG14-PadE6)") (class "Default")
      (node (ref "U1") (pin "E6") (pinfunction "PG14_E6") (pintype "bidirectional"))
    )
    (net (code "139") (name "unconnected-(U1B-PG15-PadC6)") (class "Default")
      (node (ref "U1") (pin "C6") (pinfunction "PG15_C6") (pintype "bidirectional"))
    )
    (net (code "140") (name "unconnected-(U1C-VLXSMPS-PadE1)") (class "Default")
      (node (ref "U1") (pin "E1") (pinfunction "VLXSMPS_E1") (pintype "power_in+no_connect"))
    )
  )
)
